# Guppy.net
KiCad netlist of a schematic drawn in Altium Designer
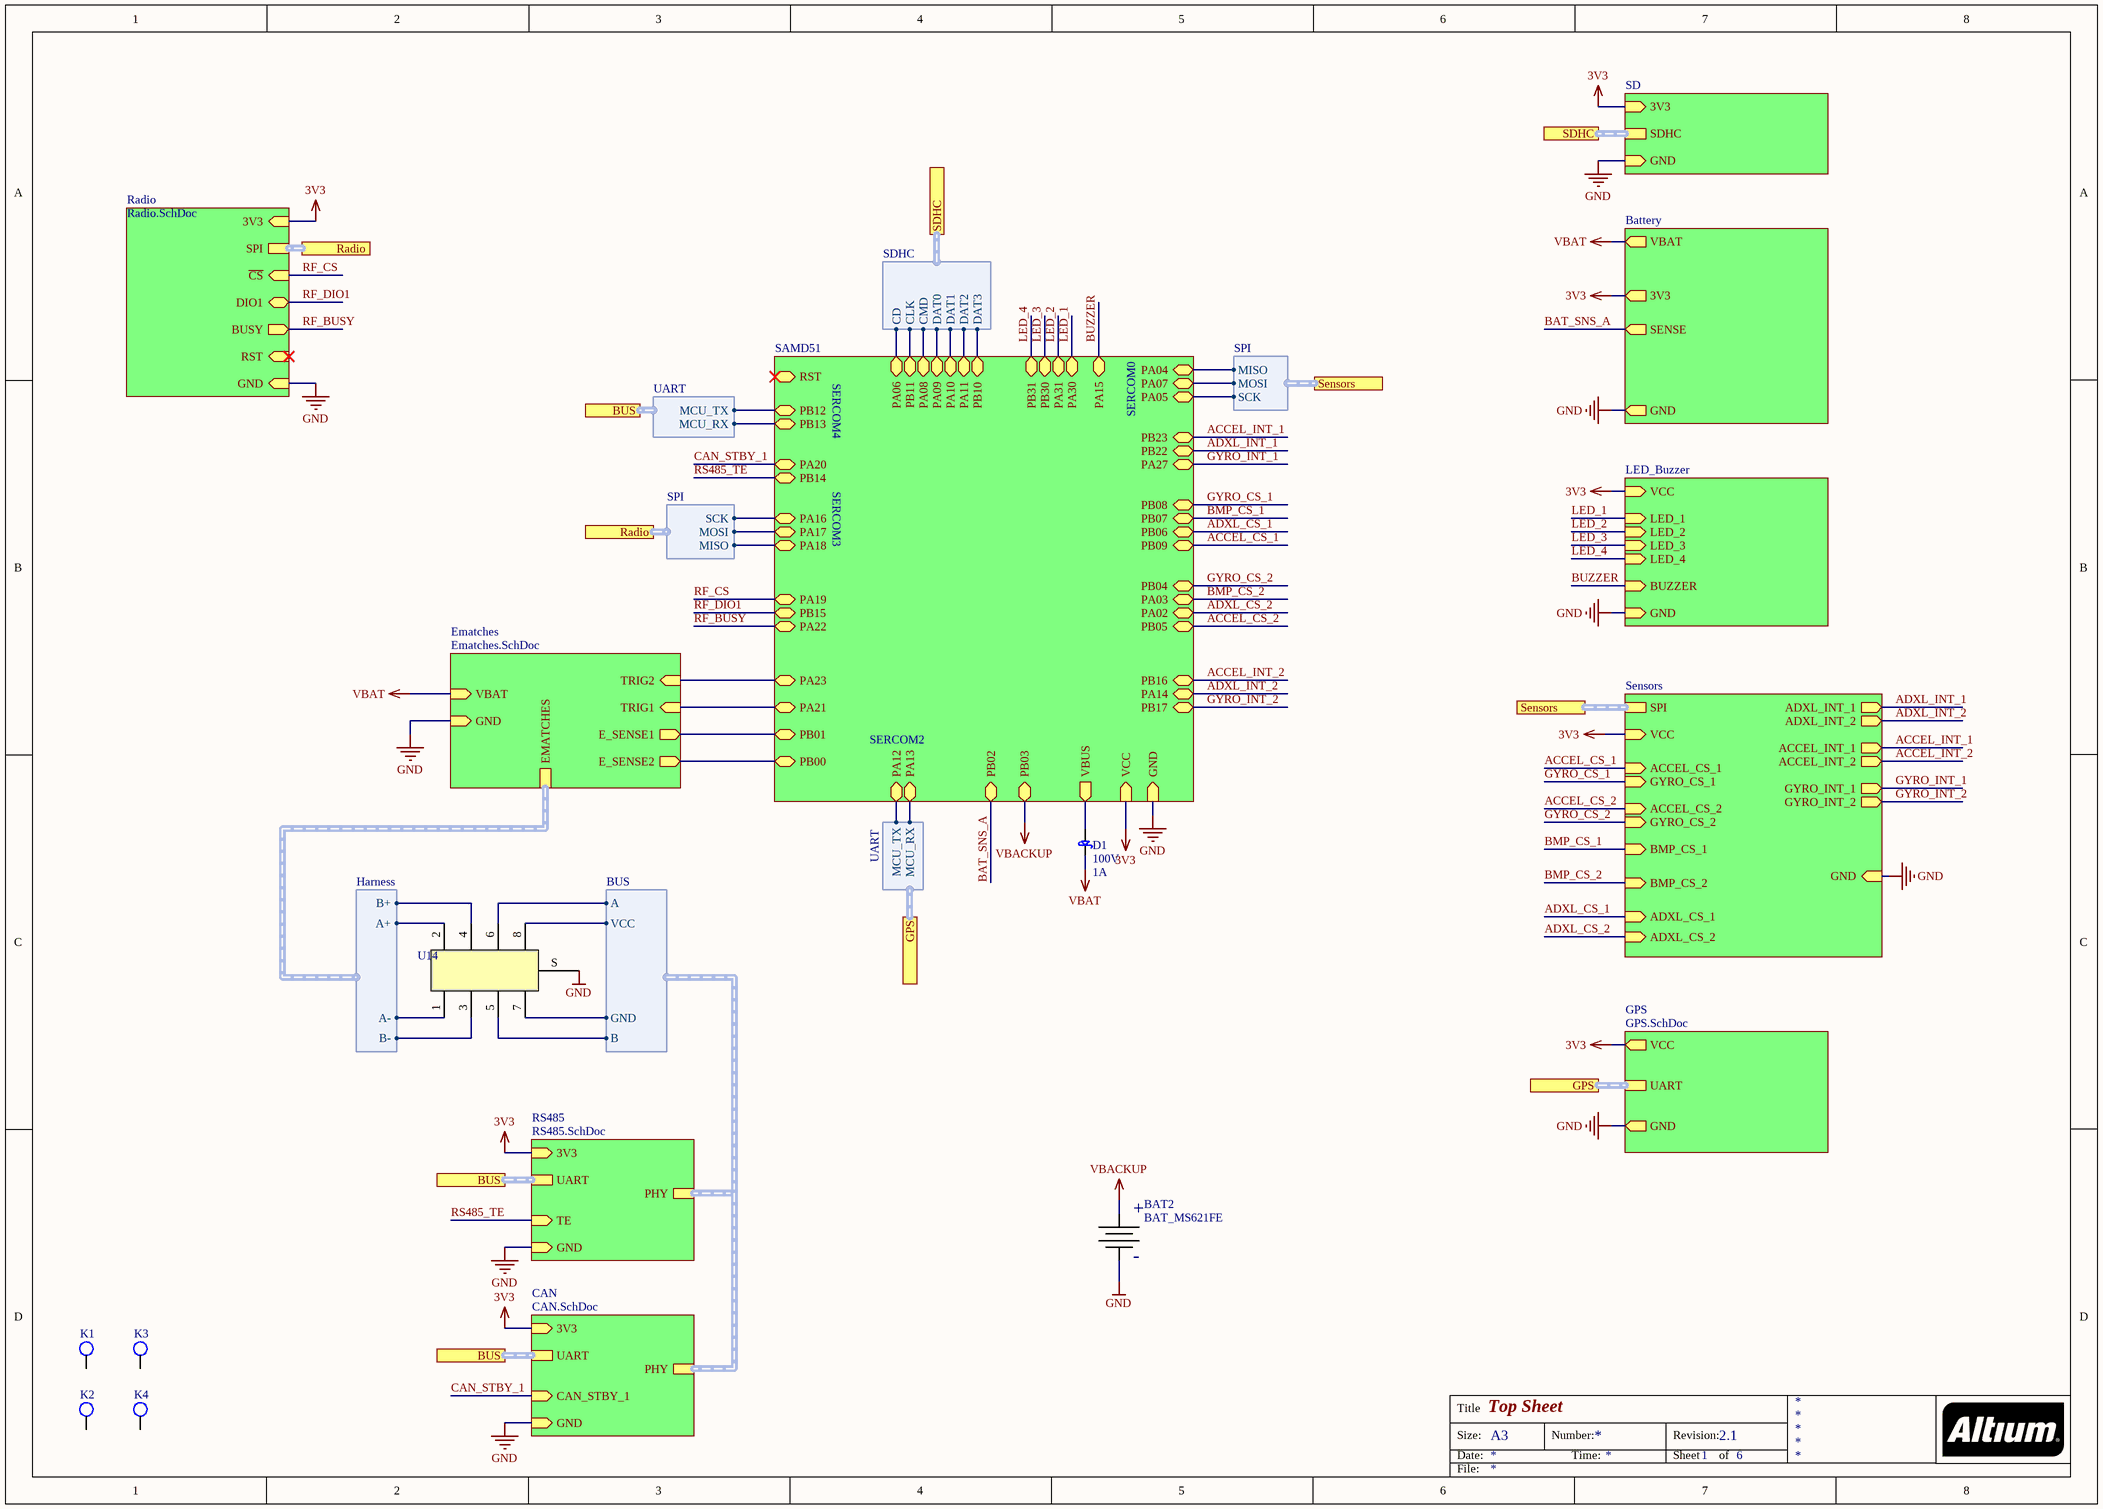
[diagram p0: Guppy.SchDoc]

(export (version "E")
  (design (tool "Eeschema 10.0.6"))
  (components
    (comp (ref "BAT2")
      (value "BAT_MS621FE")
      (footprint "BATT_COINCELL_RECHARGEABLE")
      (description "MS621FE RECHARGEABLE COIN CELL BACKUP")
      (fields
        (field (name "MANUFACTURER") "Seiko Instruments")
        (field (name "MANUFACTURER PART NUMBER") "MS621FE-FL11E")
      )
      (libsource (lib "Stanford Student Space Initiative") (part "BAT_MS621FE"))
    )
    (comp (ref "D1")
      (value "Diode_CD214A-B1100LF")
      (footprint "SMA")
      (description "Diode Schottky 100V 1A Surface Mount SMA (DO-214AC)")
      (fields
        (field (name "MANUFACTURER PART NUMBER") "CD214A-B1100LF")
        (field (name "VOLTAGE - DC REVERSE (VR) (MAX)") "100V")
        (field (name "CURRENT - AVERAGE RECTIFIED (IO)") "1A")
        (field (name "MANUFACTURER") "Bourns Inc.")
      )
      (libsource (lib "Stanford Student Space Initiative") (part "Diode_CD214A-B1100LF"))
    )
    (comp (ref "K1")
      (value "#4_PRESSFIT_MOUNTING_FOOT")
      (footprint "#4_PRESSFIT_FOOT_1/4")
      (description "Press-Fit Unthreaded Spacers, 7/32\" OD, 1/8\" Long")
      (libsource (lib "Stanford Student Space Initiative") (part "#4_PRESSFIT_MOUNTING_FOOT"))
    )
    (comp (ref "K2")
      (value "#4_PRESSFIT_MOUNTING_FOOT")
      (footprint "#4_PRESSFIT_FOOT_1/4")
      (description "Press-Fit Unthreaded Spacers, 7/32\" OD, 1/8\" Long")
      (libsource (lib "Stanford Student Space Initiative") (part "#4_PRESSFIT_MOUNTING_FOOT"))
    )
    (comp (ref "K3")
      (value "#4_PRESSFIT_MOUNTING_FOOT")
      (footprint "#4_PRESSFIT_FOOT_1/4")
      (description "Press-Fit Unthreaded Spacers, 7/32\" OD, 1/8\" Long")
      (libsource (lib "Stanford Student Space Initiative") (part "#4_PRESSFIT_MOUNTING_FOOT"))
    )
    (comp (ref "K4")
      (value "#4_PRESSFIT_MOUNTING_FOOT")
      (footprint "#4_PRESSFIT_FOOT_1/4")
      (description "Press-Fit Unthreaded Spacers, 7/32\" OD, 1/8\" Long")
      (libsource (lib "Stanford Student Space Initiative") (part "#4_PRESSFIT_MOUNTING_FOOT"))
    )
    (comp (ref "U14")
      (value "CONN 2x4 HARWIN M80-5S20805MD")
      (footprint "M80-5S20805MD")
      (libsource (lib "Stanford Student Space Initiative") (part "CONN 2x4 HARWIN M80-5S20805MD"))
    )
  )
  (nets
    (net (code "6") (name "/A") (class "Default")
      (node (ref "U14") (pin "6") (pinfunction "6_6") (pintype "passive"))
    )
    (net (code "7") (name "/A+") (class "Default")
      (node (ref "U14") (pin "2") (pinfunction "2_2") (pintype "passive"))
    )
    (net (code "8") (name "/A-") (class "Default")
      (node (ref "U14") (pin "1") (pinfunction "1_1") (pintype "passive"))
    )
    (net (code "17") (name "/B") (class "Default")
      (node (ref "U14") (pin "5") (pinfunction "5_5") (pintype "passive"))
    )
    (net (code "18") (name "/B+") (class "Default")
      (node (ref "U14") (pin "4") (pinfunction "4_4") (pintype "passive"))
    )
    (net (code "19") (name "/B-") (class "Default")
      (node (ref "U14") (pin "3") (pinfunction "3_3") (pintype "passive"))
    )
    (net (code "60") (name "/VBUS") (class "Default")
      (node (ref "D1") (pin "1") (pinfunction "Anode_1") (pintype "passive"))
    )
    (net (code "61") (name "/VCC") (class "Default")
      (node (ref "U14") (pin "8") (pinfunction "8_8") (pintype "passive"))
    )
    (net (code "68") (name "GND") (class "Default")
      (node (ref "BAT2") (pin "-") (pintype "passive"))
      (node (ref "U14") (pin "S") (pinfunction "S_S") (pintype "passive"))
    )
    (net (code "69") (name "VBACKUP") (class "Default") (node (ref "BAT2") (pin "+") (pintype "passive")))
    (net (code "70") (name "VBAT") (class "Default")
      (node (ref "D1") (pin "2") (pinfunction "Cathode_2") (pintype "passive"))
    )
    (net (code "71") (name "unconnected-(K1-Pad1)") (class "Default")
      (node (ref "K1") (pin "1") (pinfunction "1_1") (pintype "passive"))
    )
    (net (code "72") (name "unconnected-(K2-Pad1)") (class "Default")
      (node (ref "K2") (pin "1") (pinfunction "1_1") (pintype "passive"))
    )
    (net (code "73") (name "unconnected-(K3-Pad1)") (class "Default")
      (node (ref "K3") (pin "1") (pinfunction "1_1") (pintype "passive"))
    )
    (net (code "74") (name "unconnected-(K4-Pad1)") (class "Default")
      (node (ref "K4") (pin "1") (pinfunction "1_1") (pintype "passive"))
    )
    (net (code "75") (name "unconnected-(U14-Pad7)") (class "Default")
      (node (ref "U14") (pin "7") (pinfunction "7_7") (pintype "passive"))
    )
  )
)
